# TinyArcBuddy1.net
KiCad netlist of a schematic drawn in EAGLE
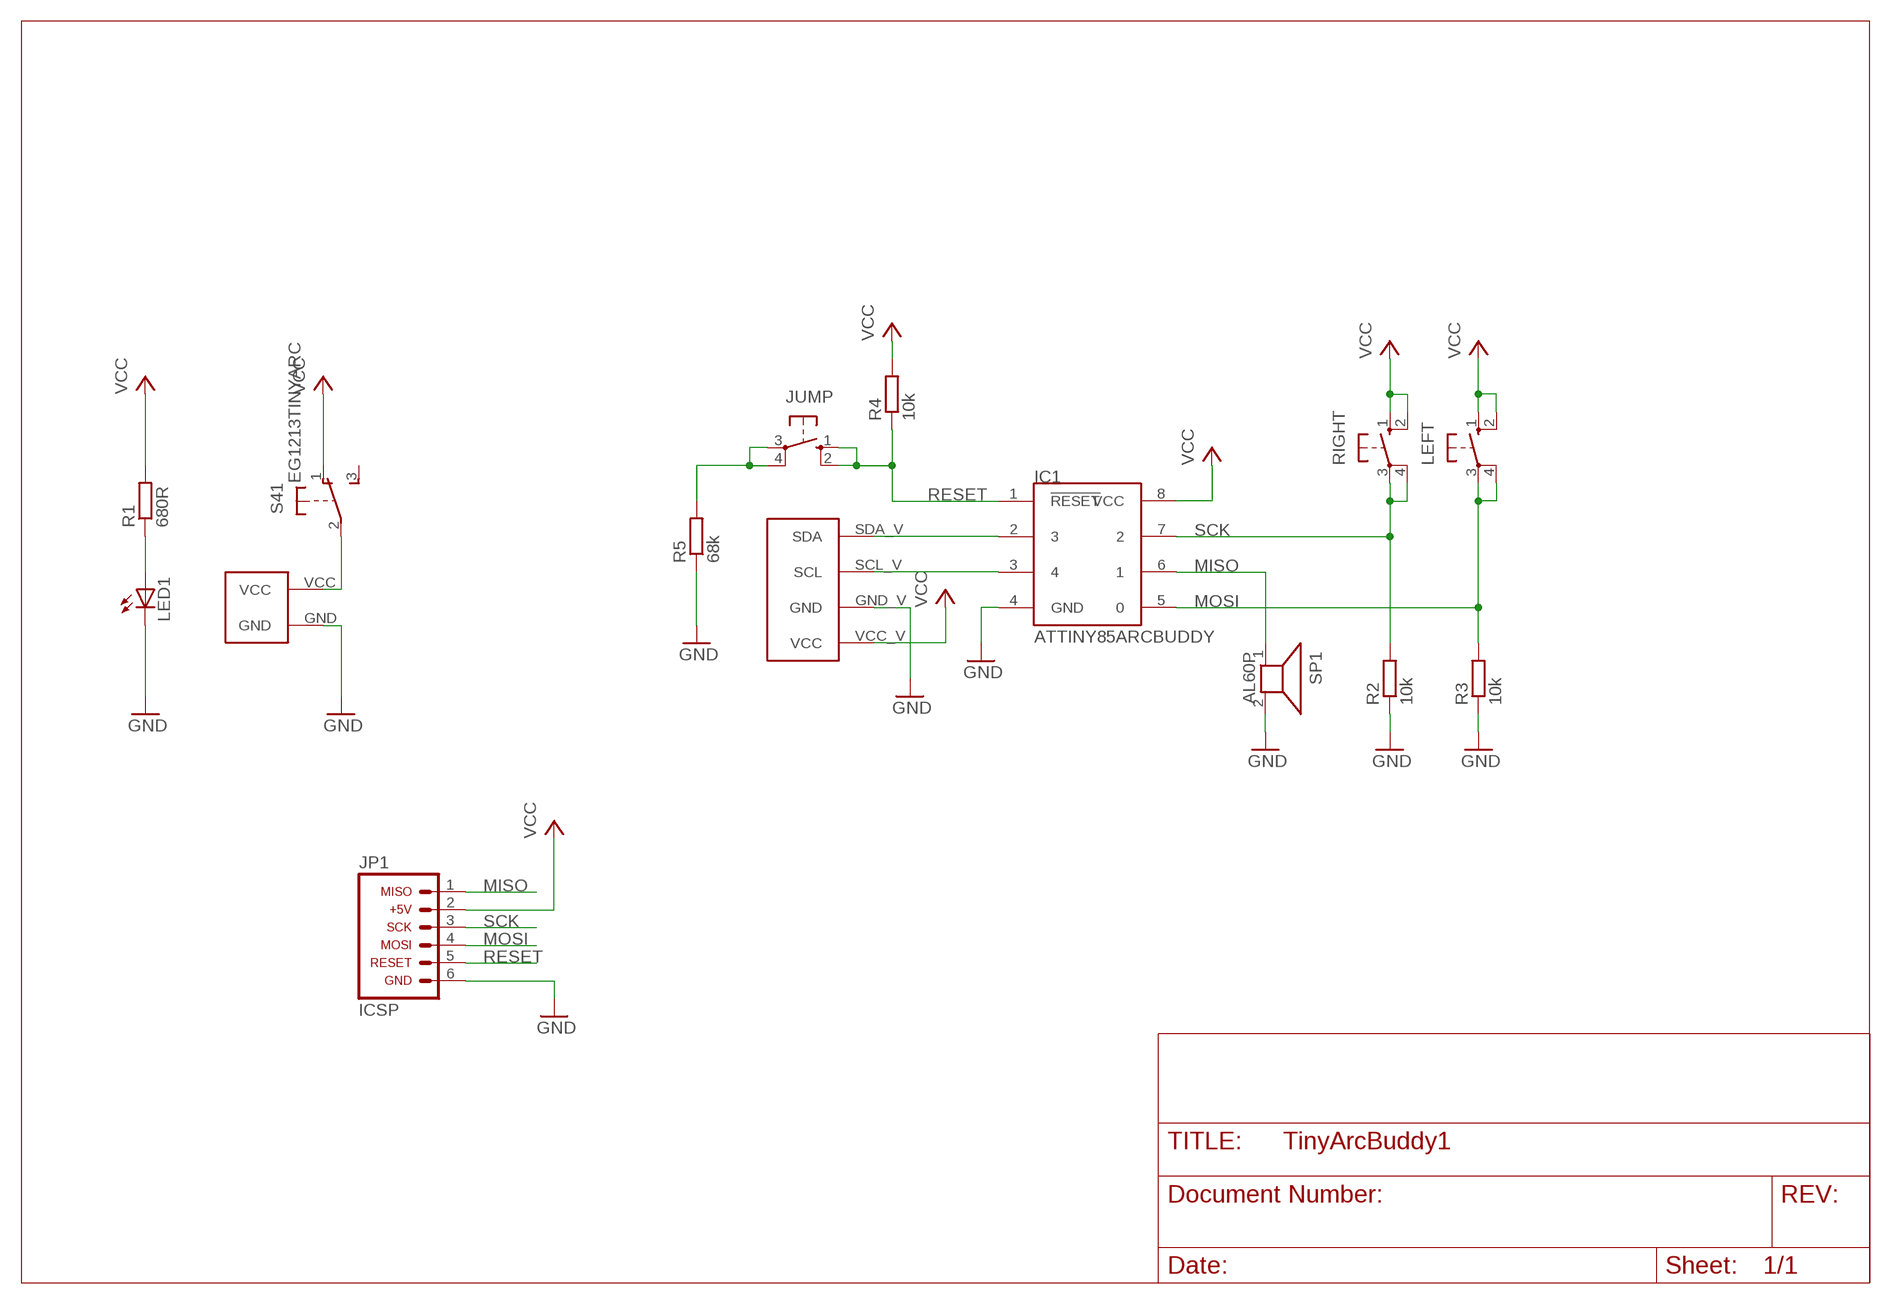
[diagram p0: schematic, sheet 1]

(export (version "E")
  (design (tool "Eeschema 10.0.6"))
  (components
    (comp (ref "IC1")
      (value "ATTINY85ARCBUDDY")
      (footprint "eagle-import:DIL08")
      (libsource (lib "eagle-import") (part "ATTINY85ARCBUDDY"))
    )
    (comp (ref "JP1")
      (value "ARDUINO_CONN-ICSPTINYARC")
      (footprint "eagle-import:CONN-2X03_TINYARC")
      (libsource (lib "eagle-import") (part "ARDUINO_CONN-ICSPTINYARC"))
    )
    (comp (ref "JUMP")
      (value "10-XX")
      (footprint "eagle-import:B3F-10XX")
      (fields (field (name "MPN") "B3F-1000"))
      (libsource (lib "eagle-import") (part "10-XX"))
    )
    (comp (ref "LED1")
      (value "LED3MM")
      (footprint "eagle-import:LED3MM")
      (libsource (lib "eagle-import") (part "LED3MM"))
    )
    (comp (ref "LEFT")
      (value "10-XX")
      (footprint "eagle-import:B3F-10XX")
      (fields (field (name "MPN") "B3F-1000"))
      (libsource (lib "eagle-import") (part "10-XX"))
    )
    (comp (ref "R1")
      (value "680R")
      (footprint "eagle-import:0207_10")
      (libsource (lib "eagle-import") (part "R-EU_0207/10"))
    )
    (comp (ref "R2")
      (value "10k")
      (footprint "eagle-import:0207_10")
      (libsource (lib "eagle-import") (part "R-EU_0207/10"))
    )
    (comp (ref "R3")
      (value "10k")
      (footprint "eagle-import:0207_10")
      (libsource (lib "eagle-import") (part "R-EU_0207/10"))
    )
    (comp (ref "R4")
      (value "10k")
      (footprint "eagle-import:0207_10")
      (libsource (lib "eagle-import") (part "R-EU_0207/10"))
    )
    (comp (ref "R5")
      (value "68k")
      (footprint "eagle-import:0207_10")
      (libsource (lib "eagle-import") (part "R-EU_0207/10"))
    )
    (comp (ref "RIGHT")
      (value "10-XX")
      (footprint "eagle-import:B3F-10XX")
      (fields (field (name "MPN") "B3F-1000"))
      (libsource (lib "eagle-import") (part "10-XX"))
    )
    (comp (ref "S4")
      (value "EG1213TINYARC")
      (footprint "eagle-import:EG1213_TINYARC")
      (libsource (lib "eagle-import") (part "EG1213TINYARC"))
    )
    (comp (ref "SP1")
      (value "AL60P")
      (footprint "eagle-import:AL60P")
      (libsource (lib "eagle-import") (part "AL60P"))
    )
    (comp (ref "U$1")
      (value "I2C_OLEDTINYARC")
      (footprint "eagle-import:I2C_OLED_PACKAGE_TINYARC")
      (libsource (lib "eagle-import") (part "I2C_OLEDTINYARC"))
    )
    (comp (ref "U$2")
      (value "CR2032")
      (footprint "eagle-import:CR2032-20MM")
      (libsource (lib "eagle-import") (part "CR2032"))
    )
  )
  (nets
    (net (code "1") (name "/MISO") (class "Default")
      (node (ref "IC1") (pin "6") (pinfunction "1_6") (pintype "bidirectional"))
      (node (ref "JP1") (pin "1") (pinfunction "1_1") (pintype "passive"))
      (node (ref "SP1") (pin "1") (pinfunction "1_1") (pintype "passive"))
    )
    (net (code "2") (name "/MOSI") (class "Default")
      (node (ref "IC1") (pin "5") (pinfunction "0_5") (pintype "bidirectional"))
      (node (ref "JP1") (pin "4") (pinfunction "4_4") (pintype "passive"))
      (node (ref "LEFT") (pin "3") (pinfunction "P_3") (pintype "passive"))
      (node (ref "LEFT") (pin "4") (pinfunction "P1_4") (pintype "passive"))
      (node (ref "R3") (pin "2") (pinfunction "2_2") (pintype "passive"))
    )
    (net (code "3") (name "/RESET") (class "Default")
      (node (ref "IC1") (pin "1") (pinfunction "~{RESET}_1") (pintype "bidirectional"))
      (node (ref "JP1") (pin "5") (pinfunction "5_5") (pintype "passive"))
      (node (ref "JUMP") (pin "1") (pinfunction "S_1") (pintype "passive"))
      (node (ref "JUMP") (pin "2") (pinfunction "S1_2") (pintype "passive"))
      (node (ref "R4") (pin "1") (pinfunction "1_1") (pintype "passive"))
    )
    (net (code "4") (name "/SCK") (class "Default")
      (node (ref "IC1") (pin "7") (pinfunction "2_7") (pintype "bidirectional"))
      (node (ref "JP1") (pin "3") (pinfunction "3_3") (pintype "passive"))
      (node (ref "R2") (pin "2") (pinfunction "2_2") (pintype "passive"))
      (node (ref "RIGHT") (pin "3") (pinfunction "P_3") (pintype "passive"))
      (node (ref "RIGHT") (pin "4") (pinfunction "P1_4") (pintype "passive"))
    )
    (net (code "5") (name "GND") (class "Default")
      (node (ref "IC1") (pin "4") (pinfunction "GND_4") (pintype "power_in"))
      (node (ref "JP1") (pin "6") (pinfunction "6_6") (pintype "passive"))
      (node (ref "LED1") (pin "K") (pinfunction "C_K") (pintype "passive"))
      (node (ref "R2") (pin "1") (pinfunction "1_1") (pintype "passive"))
      (node (ref "R3") (pin "1") (pinfunction "1_1") (pintype "passive"))
      (node (ref "R5") (pin "1") (pinfunction "1_1") (pintype "passive"))
      (node (ref "SP1") (pin "2") (pinfunction "2_2") (pintype "passive"))
      (node (ref "U$1") (pin "GND_V") (pinfunction "GND_GND_V") (pintype "bidirectional"))
      (node (ref "U$2") (pin "GND") (pinfunction "GND_GND") (pintype "bidirectional"))
    )
    (net (code "6") (name "Net-(IC1-3)") (class "Default")
      (node (ref "IC1") (pin "2") (pinfunction "3_2") (pintype "bidirectional"))
      (node (ref "U$1") (pin "SDA_V") (pinfunction "SDA_SDA_V") (pintype "bidirectional"))
    )
    (net (code "7") (name "Net-(IC1-4)") (class "Default")
      (node (ref "IC1") (pin "3") (pinfunction "4_3") (pintype "bidirectional"))
      (node (ref "U$1") (pin "SCL_V") (pinfunction "SCL_SCL_V") (pintype "bidirectional"))
    )
    (net (code "8") (name "Net-(JUMP-P)") (class "Default")
      (node (ref "JUMP") (pin "3") (pinfunction "P_3") (pintype "passive"))
      (node (ref "JUMP") (pin "4") (pinfunction "P1_4") (pintype "passive"))
      (node (ref "R5") (pin "2") (pinfunction "2_2") (pintype "passive"))
    )
    (net (code "9") (name "Net-(LED1-PadA)") (class "Default")
      (node (ref "LED1") (pin "A") (pinfunction "A_A") (pintype "passive"))
      (node (ref "R1") (pin "1") (pinfunction "1_1") (pintype "passive"))
    )
    (net (code "10") (name "Net-(S4A-P)") (class "Default")
      (node (ref "S4") (pin "2") (pinfunction "P_2") (pintype "passive"))
      (node (ref "U$2") (pin "VCC") (pinfunction "VCC_VCC") (pintype "bidirectional"))
    )
    (net (code "11") (name "VCC") (class "Default")
      (node (ref "IC1") (pin "8") (pinfunction "VCC_8") (pintype "power_in"))
      (node (ref "JP1") (pin "2") (pinfunction "2_2") (pintype "passive"))
      (node (ref "LEFT") (pin "1") (pinfunction "S_1") (pintype "passive"))
      (node (ref "LEFT") (pin "2") (pinfunction "S1_2") (pintype "passive"))
      (node (ref "R1") (pin "2") (pinfunction "2_2") (pintype "passive"))
      (node (ref "R4") (pin "2") (pinfunction "2_2") (pintype "passive"))
      (node (ref "RIGHT") (pin "1") (pinfunction "S_1") (pintype "passive"))
      (node (ref "RIGHT") (pin "2") (pinfunction "S1_2") (pintype "passive"))
      (node (ref "S4") (pin "1") (pinfunction "O_1") (pintype "passive"))
      (node (ref "U$1") (pin "VCC_V") (pinfunction "VCC_VCC_V") (pintype "bidirectional"))
    )
    (net (code "12") (name "unconnected-(S4A-S-Pad3)") (class "Default")
      (node (ref "S4") (pin "3") (pinfunction "S_3") (pintype "passive"))
    )
  )
)
